# Capteurs_Schematic.net
KiCad netlist of a schematic drawn in Altium Designer
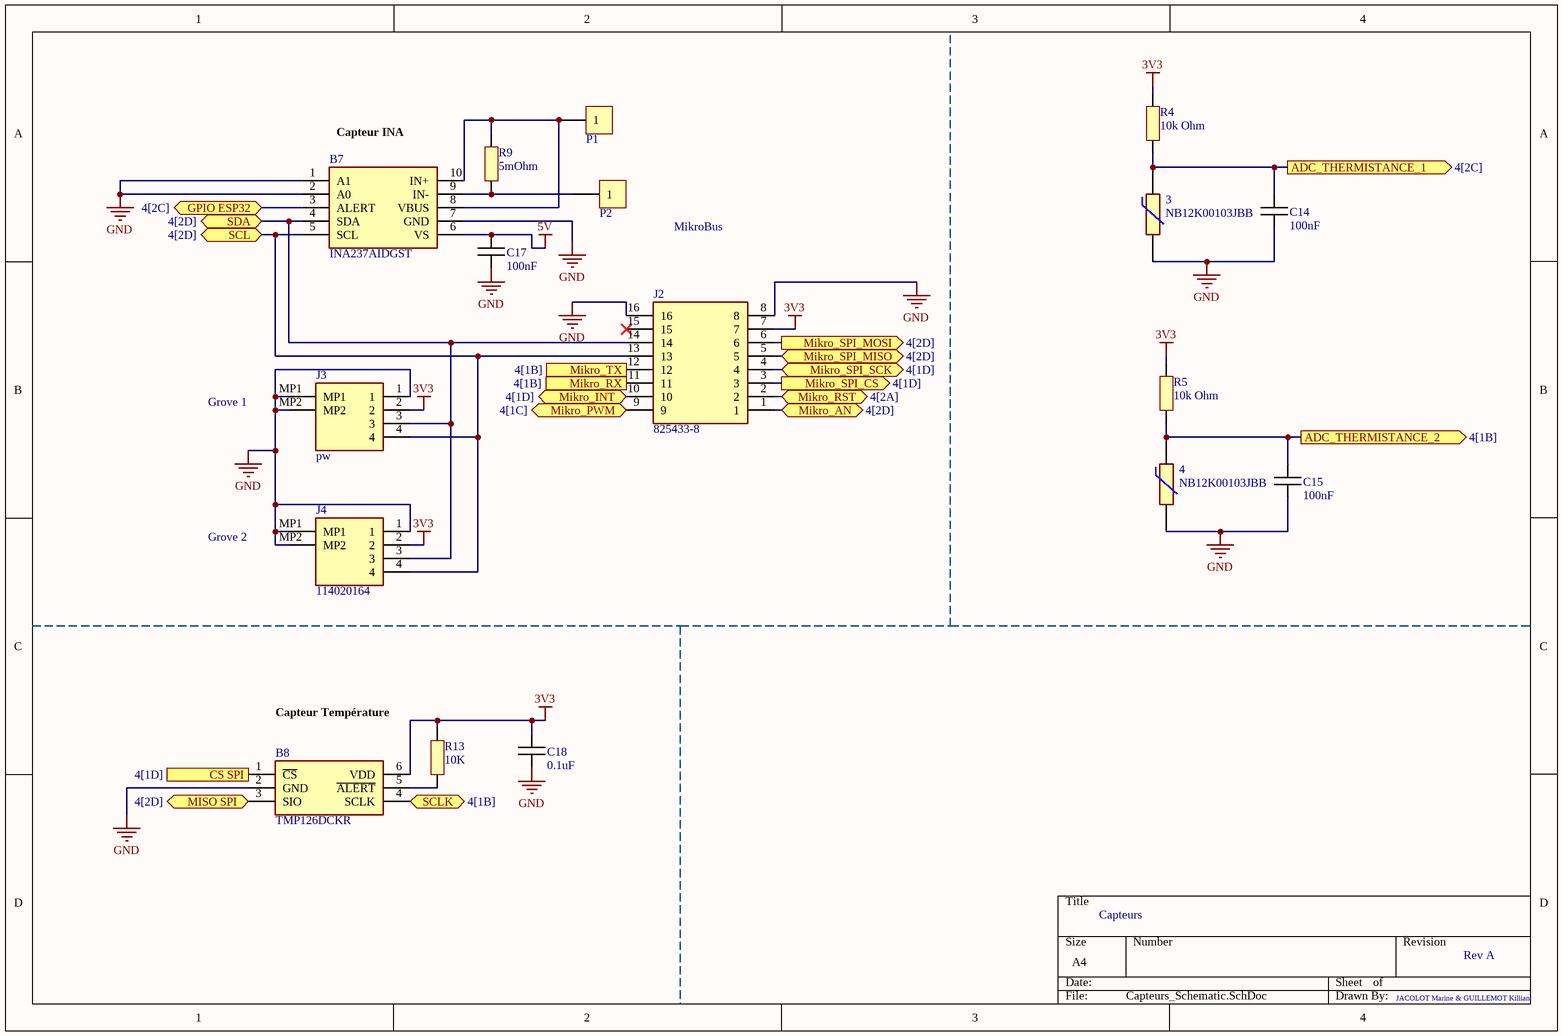
[diagram p0: Capteurs_Schematic.SchDoc]

(export (version "E")
  (design (tool "Eeschema 10.0.6"))
  (components
    (comp (ref "3")
      (value "NB12K00103JBB")
      (footprint "RESC2212X50N")
      (description "NTC SMD Thermistor, NB12K, 10K, 5% AVX 10k 0805 Protection NTC Thermistor, 5s, 2 x 1.25 x 1.3mm")
      (fields (field (name "MOUSER PART NUMBER") "581-NB12K00103JBB"))
      (libsource (lib "SCHLibrary") (part "NB12K00103JBB"))
    )
    (comp (ref "4")
      (value "NB12K00103JBB")
      (footprint "RESC2212X50N")
      (description "NTC SMD Thermistor, NB12K, 10K, 5% AVX 10k 0805 Protection NTC Thermistor, 5s, 2 x 1.25 x 1.3mm")
      (fields (field (name "MOUSER PART NUMBER") "581-NB12K00103JBB"))
      (libsource (lib "SCHLibrary") (part "NB12K00103JBB"))
    )
    (comp (ref "B7")
      (value "INA237AIDGST")
      (footprint "SOP50P490X110-10N")
      (fields (field (name "MOUSER PART NUMBER") "595-INA237AIDGST"))
      (libsource (lib "SCHLibrary") (part "INA237AIDGST"))
    )
    (comp (ref "B8")
      (value "TMP126DCKR")
      (footprint "SOT65P210X110-6N")
      (fields (field (name "MOUSER PART NUMBER") "595-TMP126DCKR"))
      (libsource (lib "SCHLibrary") (part "TMP126DCKR"))
    )
    (comp (ref "C14")
      (value "100nF")
      (footprint "CAPC1005X06N")
      (libsource (lib "SCHLibrary") (part "Capacitor"))
    )
    (comp (ref "C15")
      (value "100nF")
      (footprint "CAPC1005X06N")
      (libsource (lib "SCHLibrary") (part "Capacitor"))
    )
    (comp (ref "C17")
      (value "100nF")
      (footprint "CAPC1005X06N")
      (libsource (lib "SCHLibrary") (part "Capacitor"))
    )
    (comp (ref "C18")
      (value "0.1uF")
      (footprint "CAPC1005X06N")
      (libsource (lib "SCHLibrary") (part "Capacitor"))
    )
    (comp (ref "J2")
      (value "825433-8")
      (footprint "Connect-Mikrobus")
      (description "Headers & Wire Housings 8P double for connection mikrobus")
      (fields (field (name "MOUSER PART NUMBER") "571-825433-8"))
      (libsource (lib "SCHLibrary") (part "Connect-Mikrobus"))
    )
    (comp (ref "J3")
      (value "pw")
      (footprint "114020164")
      (description "Seeed Studio Accessories Grove Female Header - SMD-4P-2.0mm-90D-20Pcs")
      (fields
        (field (name "MANUFACTURER_PART_NUMBER") "114020164")
        (field (name "MOUSER PART NUMBER") "713-114020164")
      )
      (libsource (lib "SCHLibrary") (part "114020164"))
    )
    (comp (ref "J4")
      (value "114020164")
      (footprint "114020164")
      (description "Seeed Studio Accessories Grove Female Header - SMD-4P-2.0mm-90D-20Pcs")
      (fields (field (name "MOUSER PART NUMBER") "713-114020164"))
      (libsource (lib "SCHLibrary") (part "114020164"))
    )
    (comp (ref "P1")
      (value "Plage CMS 10x5")
      (footprint "Plage CMS 10x5")
      (description "Plage de report CMS 10x5mm")
      (libsource (lib "SCHLibrary") (part "Plage CMS 10x5"))
    )
    (comp (ref "P2")
      (value "Plage CMS 10x5")
      (footprint "Plage CMS 10x5")
      (description "Plage de report CMS 10x5mm")
      (libsource (lib "SCHLibrary") (part "Plage CMS 10x5"))
    )
    (comp (ref "R4")
      (value "10k Ohm")
      (footprint "RESC1005X06N")
      (libsource (lib "SCHLibrary") (part "Resistor"))
    )
    (comp (ref "R5")
      (value "10k Ohm")
      (footprint "RESC1005X06N")
      (libsource (lib "SCHLibrary") (part "Resistor"))
    )
    (comp (ref "R9") (value "5mOhm") (footprint "RESC1005X06N") (libsource (lib "") (part "Resistor_1")))
    (comp (ref "R13") (value "10K") (footprint "RESC1005X06N") (libsource (lib "") (part "Resistor_1")))
  )
  (nets
    (net (code "1") (name "/ADC_THERMISTANCE_1") (class "Default")
      (node (ref "3") (pin "1") (pinfunction "1_1") (pintype "passive"))
      (node (ref "C14") (pin "1") (pinfunction "1_1") (pintype "passive"))
      (node (ref "R4") (pin "2") (pinfunction "2_2") (pintype "passive"))
    )
    (net (code "2") (name "/ADC_THERMISTANCE_2") (class "Default")
      (node (ref "4") (pin "1") (pinfunction "1_1") (pintype "passive"))
      (node (ref "C15") (pin "1") (pinfunction "1_1") (pintype "passive"))
      (node (ref "R5") (pin "2") (pinfunction "2_2") (pintype "passive"))
    )
    (net (code "3") (name "/CS SPI") (class "Default")
      (node (ref "B8") (pin "1") (pinfunction "~{CS}_1") (pintype "passive"))
    )
    (net (code "4") (name "/GPIO ESP32") (class "Default")
      (node (ref "B7") (pin "3") (pinfunction "ALERT_3") (pintype "passive"))
    )
    (net (code "5") (name "/MISO SPI") (class "Default")
      (node (ref "B8") (pin "3") (pinfunction "SIO_3") (pintype "passive"))
    )
    (net (code "6") (name "/Mikro_AN") (class "Default")
      (node (ref "J2") (pin "1") (pinfunction "1_1") (pintype "passive"))
    )
    (net (code "7") (name "/Mikro_INT") (class "Default")
      (node (ref "J2") (pin "10") (pinfunction "10_10") (pintype "passive"))
    )
    (net (code "8") (name "/Mikro_PWM") (class "Default")
      (node (ref "J2") (pin "9") (pinfunction "9_9") (pintype "passive"))
    )
    (net (code "9") (name "/Mikro_RST") (class "Default")
      (node (ref "J2") (pin "2") (pinfunction "2_2") (pintype "passive"))
    )
    (net (code "10") (name "/Mikro_RX") (class "Default")
      (node (ref "J2") (pin "11") (pinfunction "11_11") (pintype "passive"))
    )
    (net (code "11") (name "/Mikro_SPI_CS") (class "Default")
      (node (ref "J2") (pin "3") (pinfunction "3_3") (pintype "passive"))
    )
    (net (code "12") (name "/Mikro_SPI_MISO") (class "Default")
      (node (ref "J2") (pin "5") (pinfunction "5_5") (pintype "passive"))
    )
    (net (code "13") (name "/Mikro_SPI_MOSI") (class "Default")
      (node (ref "J2") (pin "6") (pinfunction "6_6") (pintype "passive"))
    )
    (net (code "14") (name "/Mikro_SPI_SCK") (class "Default")
      (node (ref "J2") (pin "4") (pinfunction "4_4") (pintype "passive"))
    )
    (net (code "15") (name "/Mikro_TX") (class "Default")
      (node (ref "J2") (pin "12") (pinfunction "12_12") (pintype "passive"))
    )
    (net (code "16") (name "/SCL") (class "Default")
      (node (ref "B7") (pin "5") (pinfunction "SCL_5") (pintype "passive"))
      (node (ref "J2") (pin "13") (pinfunction "13_13") (pintype "passive"))
      (node (ref "J3") (pin "4") (pinfunction "4_4") (pintype "passive"))
      (node (ref "J4") (pin "4") (pinfunction "4_4") (pintype "passive"))
    )
    (net (code "17") (name "/SCLK") (class "Default")
      (node (ref "B8") (pin "4") (pinfunction "SCLK_4") (pintype "passive"))
    )
    (net (code "18") (name "/SDA") (class "Default")
      (node (ref "B7") (pin "4") (pinfunction "SDA_4") (pintype "passive"))
      (node (ref "J2") (pin "14") (pinfunction "14_14") (pintype "passive"))
      (node (ref "J3") (pin "3") (pinfunction "3_3") (pintype "passive"))
      (node (ref "J4") (pin "3") (pinfunction "3_3") (pintype "passive"))
    )
    (net (code "19") (name "3V3") (class "Default")
      (node (ref "B8") (pin "6") (pinfunction "VDD_6") (pintype "passive"))
      (node (ref "C18") (pin "1") (pinfunction "1_1") (pintype "passive"))
      (node (ref "J2") (pin "7") (pinfunction "7_7") (pintype "passive"))
      (node (ref "J3") (pin "2") (pinfunction "2_2") (pintype "passive"))
      (node (ref "J4") (pin "2") (pinfunction "2_2") (pintype "passive"))
      (node (ref "R13") (pin "2") (pinfunction "2_2") (pintype "passive"))
      (node (ref "R4") (pin "1") (pinfunction "1_1") (pintype "passive"))
      (node (ref "R5") (pin "1") (pinfunction "1_1") (pintype "passive"))
    )
    (net (code "20") (name "5V") (class "Default")
      (node (ref "B7") (pin "6") (pinfunction "VS_6") (pintype "passive"))
      (node (ref "C17") (pin "1") (pinfunction "1_1") (pintype "passive"))
    )
    (net (code "21") (name "GND") (class "Default")
      (node (ref "3") (pin "2") (pinfunction "2_2") (pintype "passive"))
      (node (ref "4") (pin "2") (pinfunction "2_2") (pintype "passive"))
      (node (ref "B7") (pin "1") (pinfunction "A1_1") (pintype "passive"))
      (node (ref "B7") (pin "2") (pinfunction "A0_2") (pintype "passive"))
      (node (ref "B7") (pin "7") (pinfunction "GND_7") (pintype "passive"))
      (node (ref "B8") (pin "2") (pinfunction "GND_2") (pintype "passive"))
      (node (ref "C14") (pin "2") (pinfunction "2_2") (pintype "passive"))
      (node (ref "C15") (pin "2") (pinfunction "2_2") (pintype "passive"))
      (node (ref "C17") (pin "2") (pinfunction "2_2") (pintype "passive"))
      (node (ref "C18") (pin "2") (pinfunction "2_2") (pintype "passive"))
      (node (ref "J2") (pin "16") (pinfunction "16_16") (pintype "passive"))
      (node (ref "J2") (pin "8") (pinfunction "8_8") (pintype "passive"))
      (node (ref "J3") (pin "1") (pinfunction "1_1") (pintype "passive"))
      (node (ref "J3") (pin "MP1") (pinfunction "MP1_MP1") (pintype "passive"))
      (node (ref "J3") (pin "MP2") (pinfunction "MP2_MP2") (pintype "passive"))
      (node (ref "J4") (pin "1") (pinfunction "1_1") (pintype "passive"))
      (node (ref "J4") (pin "MP1") (pinfunction "MP1_MP1") (pintype "passive"))
      (node (ref "J4") (pin "MP2") (pinfunction "MP2_MP2") (pintype "passive"))
    )
    (net (code "22") (name "Net-(B7-IN+)") (class "Default")
      (node (ref "B7") (pin "10") (pinfunction "IN+_10") (pintype "passive"))
      (node (ref "B7") (pin "8") (pinfunction "VBUS_8") (pintype "passive"))
      (node (ref "P1") (pin "1") (pinfunction "1_1") (pintype "passive"))
      (node (ref "R9") (pin "2") (pinfunction "2_2") (pintype "passive"))
    )
    (net (code "23") (name "Net-(B7-IN-)") (class "Default")
      (node (ref "B7") (pin "9") (pinfunction "IN-_9") (pintype "passive"))
      (node (ref "P2") (pin "1") (pinfunction "1_1") (pintype "passive"))
      (node (ref "R9") (pin "1") (pinfunction "1_1") (pintype "passive"))
    )
    (net (code "24") (name "Net-(B8-~{ALERT})") (class "Default")
      (node (ref "B8") (pin "5") (pinfunction "~{ALERT}_5") (pintype "passive"))
      (node (ref "R13") (pin "1") (pinfunction "1_1") (pintype "passive"))
    )
    (net (code "25") (name "unconnected-(J2-Pad15)") (class "Default")
      (node (ref "J2") (pin "15") (pinfunction "15_15") (pintype "passive+no_connect"))
    )
  )
)
